# Ports.net
KiCad netlist of a schematic drawn in Altium Designer
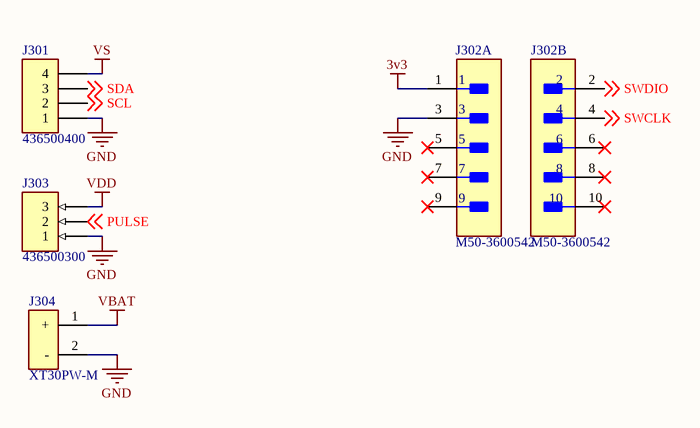
[diagram p0: Ports.SchDoc]

(export (version "E")
  (design (tool "Eeschema 10.0.6"))
  (components
    (comp (ref "J301")
      (value "436500400")
      (footprint "436500400")
      (libsource (lib "Main") (part "436500400"))
    )
    (comp (ref "J302")
      (value "M50-3600542")
      (footprint "FP-M50-3600542-MFG")
      (description "CONN HEADER SMD 10POS 1.27MM")
      (libsource (lib "Main") (part "M50-3600542"))
    )
    (comp (ref "J303")
      (value "436500300")
      (footprint "436500300")
      (libsource (lib "Main") (part "436500300"))
    )
    (comp (ref "J304") (value "XT30PW-M") (footprint "XT30PW-M") (libsource (lib "Main") (part "XT30PW-M")))
  )
  (nets
    (net (code "1") (name "3v3") (class "Default")
      (node (ref "J302") (pin "1") (pinfunction "1_1") (pintype "passive"))
    )
    (net (code "2") (name "GND") (class "Default")
      (node (ref "J301") (pin "1") (pinfunction "1_1") (pintype "passive"))
      (node (ref "J302") (pin "3") (pinfunction "3_3") (pintype "passive"))
      (node (ref "J303") (pin "1") (pinfunction "1_1") (pintype "input"))
      (node (ref "J304") (pin "2") (pinfunction "-_2") (pintype "power_in"))
    )
    (net (code "3") (name "PULSE") (class "Default")
      (node (ref "J303") (pin "2") (pinfunction "2_2") (pintype "input"))
    )
    (net (code "4") (name "SCL") (class "Default")
      (node (ref "J301") (pin "2") (pinfunction "2_2") (pintype "passive"))
    )
    (net (code "5") (name "SDA") (class "Default")
      (node (ref "J301") (pin "3") (pinfunction "3_3") (pintype "passive"))
    )
    (net (code "6") (name "SWCLK") (class "Default")
      (node (ref "J302") (pin "4") (pinfunction "4_4") (pintype "passive"))
    )
    (net (code "7") (name "SWDIO") (class "Default")
      (node (ref "J302") (pin "2") (pinfunction "2_2") (pintype "passive"))
    )
    (net (code "8") (name "VBAT") (class "Default")
      (node (ref "J304") (pin "1") (pinfunction "+_1") (pintype "power_in"))
    )
    (net (code "9") (name "VDD") (class "Default")
      (node (ref "J303") (pin "3") (pinfunction "3_3") (pintype "input"))
    )
    (net (code "10") (name "VS") (class "Default")
      (node (ref "J301") (pin "4") (pinfunction "4_4") (pintype "passive"))
    )
    (net (code "11") (name "unconnected-(J302-Pad5)") (class "Default")
      (node (ref "J302") (pin "5") (pinfunction "5_5") (pintype "passive+no_connect"))
    )
    (net (code "12") (name "unconnected-(J302-Pad6)") (class "Default")
      (node (ref "J302") (pin "6") (pinfunction "6_6") (pintype "passive+no_connect"))
    )
    (net (code "13") (name "unconnected-(J302-Pad7)") (class "Default")
      (node (ref "J302") (pin "7") (pinfunction "7_7") (pintype "passive+no_connect"))
    )
    (net (code "14") (name "unconnected-(J302-Pad8)") (class "Default")
      (node (ref "J302") (pin "8") (pinfunction "8_8") (pintype "passive+no_connect"))
    )
    (net (code "15") (name "unconnected-(J302-Pad9)") (class "Default")
      (node (ref "J302") (pin "9") (pinfunction "9_9") (pintype "passive+no_connect"))
    )
    (net (code "16") (name "unconnected-(J302-Pad10)") (class "Default")
      (node (ref "J302") (pin "10") (pinfunction "10_10") (pintype "passive+no_connect"))
    )
  )
)
